# PG04__BALANCER.net
KiCad netlist of a schematic drawn in Altium Designer
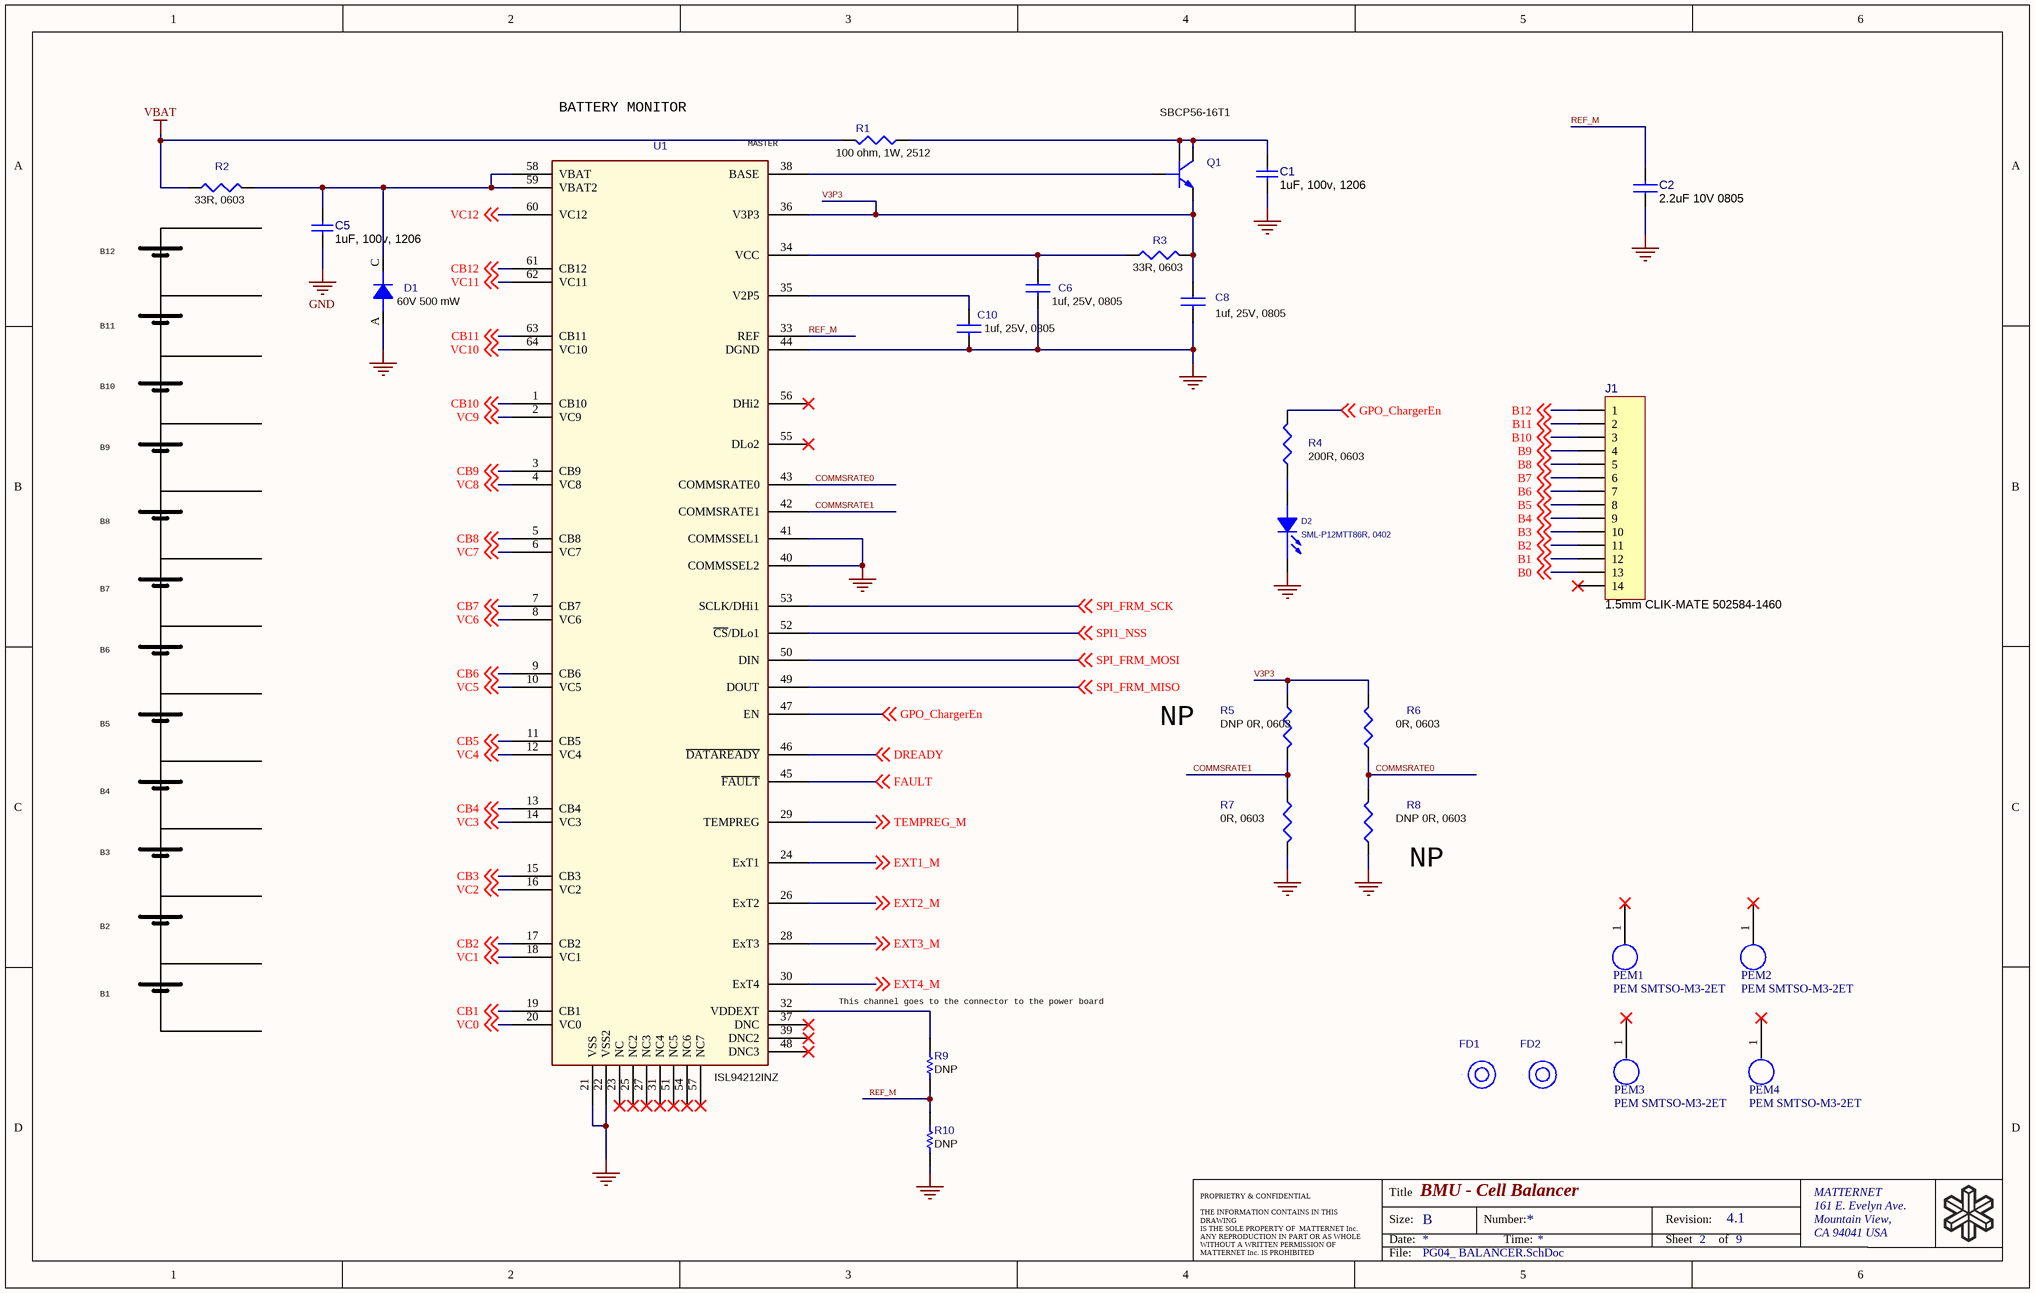
[diagram p0: PG04_ BALANCER.SchDoc]

(export (version "E")
  (design (tool "Eeschema 10.0.6"))
  (components
    (comp (ref "C1")
      (value "1uF, 100v, 1206")
      (footprint "C1206")
      (description "CAP CER 1UF 100V X7R 1210 AUTO F")
      (fields
        (field (name "MANUFACTURER") "KEMET")
        (field (name "MANUFACTURER PART NUMBER") "C1210X105K1RACAUTO")
      )
      (libsource (lib "Miscellaneous Devices") (part "Cap"))
    )
    (comp (ref "C2")
      (value "2.2uF 10V 0805")
      (footprint "C0805")
      (description "CAP CER 2.2UF 10V 10% X7R 0805")
      (fields
        (field (name "MANUFACTURER") "KEMET")
        (field (name "MANUFACTURER PART NUMBER") "C0805X225K8RACAUTO")
      )
      (libsource (lib "*") (part "CAP-Generic-0805"))
    )
    (comp (ref "C5")
      (value "1uF, 100v, 1206")
      (footprint "C1206")
      (description "CAP CER 1UF 100V X7R 1210 AUTO F")
      (fields
        (field (name "MANUFACTURER") "KEMET")
        (field (name "MANUFACTURER PART NUMBER") "C1210X105K1RACAUTO")
      )
      (libsource (lib "Miscellaneous Devices") (part "Cap"))
    )
    (comp (ref "C6")
      (value "1uf, 25V, 0805")
      (footprint "C0805")
      (description "CAP CER 1UF 25V X7R 0805")
      (fields
        (field (name "MANUFACTURER") "Murata")
        (field (name "MANUFACTURER PART NUMBER") "GCJ21BR71E105KA12L")
      )
      (libsource (lib "*") (part "CAP-Generic-0402"))
    )
    (comp (ref "C8")
      (value "1uf, 25V, 0805")
      (footprint "C0805")
      (description "CAP CER 1UF 25V X7R 0805")
      (fields
        (field (name "MANUFACTURER") "Murata")
        (field (name "MANUFACTURER PART NUMBER") "GCJ21BR71E105KA12L")
      )
      (libsource (lib "*") (part "CAP-Generic-0402"))
    )
    (comp (ref "C10")
      (value "1uf, 25V, 0805")
      (footprint "C0805")
      (description "CAP CER 1UF 25V X7R 0805")
      (fields
        (field (name "MANUFACTURER") "Murata")
        (field (name "MANUFACTURER PART NUMBER") "GCJ21BR71E105KA12L")
      )
      (libsource (lib "*") (part "CAP-Generic-0402"))
    )
    (comp (ref "D1")
      (value "60V 500 mW")
      (footprint "SOD-123")
      (description "DIODE ZENER 60V 500MW SOD123")
      (fields
        (field (name "MANUFACTURER") "ON Semiconductor")
        (field (name "MANUFACTURER PART NUMBER") "MMSZ5264BT1G")
      )
      (libsource (lib "*") (part "DIO-GENERIC"))
    )
    (comp (ref "D2")
      (value "SML-P12MTT86R, 0402")
      (footprint "D0402")
      (libsource (lib "M2_V8_BMU_V1.0") (part "LED-GENERIC"))
    )
    (comp (ref "FD1")
      (value "FIDUCIAL_REF")
      (footprint "FIDUCIAL_REFDES")
      (libsource (lib "*") (part "FIDUCIAL_REF"))
    )
    (comp (ref "FD2")
      (value "FIDUCIAL_REF")
      (footprint "FIDUCIAL_REFDES")
      (libsource (lib "*") (part "FIDUCIAL_REF"))
    )
    (comp (ref "J1")
      (value "1.5mm CLIK-MATE 502584-1460")
      (footprint "CONN14_1p5mm_SM")
      (description "CONN RCPT 14POS 0.059 TIN SMD")
      (fields (field (name "MANUFACTURER") "Molex") (field (name "MANUFACTURER PART NUMBER") "502584-1460"))
      (libsource (lib "Miscellaneous Connectors") (part "Header 14"))
    )
    (comp (ref "PEM1")
      (value "PEM SMTSO-M3-2ET")
      (footprint "SMTSO-M3-2ET")
      (description "PEM Nut, M3 thread")
      (libsource (lib "RonsLib1") (part "PEM SMTSO-M3-2ET"))
    )
    (comp (ref "PEM2")
      (value "PEM SMTSO-M3-2ET")
      (footprint "SMTSO-M3-2ET")
      (description "PEM Nut, M3 thread")
      (libsource (lib "RonsLib1") (part "PEM SMTSO-M3-2ET"))
    )
    (comp (ref "PEM3")
      (value "PEM SMTSO-M3-2ET")
      (footprint "SMTSO-M3-2ET")
      (description "PEM Nut, M3 thread")
      (libsource (lib "RonsLib1") (part "PEM SMTSO-M3-2ET"))
    )
    (comp (ref "PEM4")
      (value "PEM SMTSO-M3-2ET")
      (footprint "SMTSO-M3-2ET")
      (description "PEM Nut, M3 thread")
      (libsource (lib "RonsLib1") (part "PEM SMTSO-M3-2ET"))
    )
    (comp (ref "Q1")
      (value "SBCP56-16T1")
      (footprint "SOT-223")
      (description "TRANS NPN 80V 1.0A SOT-223")
      (fields
        (field (name "MANUFACTURER") "ON Semiconductor")
        (field (name "MANUFACTURER PART NUMBER") "SBCP56-16T1G")
      )
      (libsource (lib "*") (part "Trans-Generic_2"))
    )
    (comp (ref "R1")
      (value "100 ohm, 1W, 2512")
      (footprint "2512")
      (description "RES SMD 100 OHM 5% 1W 2512")
      (fields
        (field (name "MANUFACTURER") "Panasonic")
        (field (name "MANUFACTURER PART NUMBER") "ERJ-1TYJ101U")
      )
      (libsource (lib "*") (part "R-Generic"))
    )
    (comp (ref "R2")
      (value "33R, 0603")
      (footprint "R0603")
      (description "RES SMD 33 OHM 1% 1/10W 0603")
      (fields
        (field (name "MANUFACTURER") "Yageo")
        (field (name "MANUFACTURER PART NUMBER") "AC0603FR-0733RL")
      )
      (libsource (lib "*") (part "R-Generic-0603"))
    )
    (comp (ref "R3")
      (value "33R, 0603")
      (footprint "R0603")
      (description "RES SMD 33 OHM 1% 1/10W 0603")
      (fields
        (field (name "MANUFACTURER") "Yageo")
        (field (name "MANUFACTURER PART NUMBER") "AC0603FR-0733RL")
      )
      (libsource (lib "*") (part "R-Generic-0603"))
    )
    (comp (ref "R4")
      (value "200R, 0603")
      (footprint "R0603")
      (description "RES SMD 200 OHM 1% 1/10W 0603")
      (fields
        (field (name "MANUFACTURER") "Yageo")
        (field (name "MANUFACTURER PART NUMBER") "AC0603FR-07200RL")
      )
      (libsource (lib "*") (part "R-Generic-0603"))
    )
    (comp (ref "R5")
      (value "DNP 0R, 0603")
      (footprint "R0603")
      (description "DNP")
      (libsource (lib "*") (part "R-Generic-0402"))
    )
    (comp (ref "R6")
      (value "0R, 0603")
      (footprint "R0603")
      (description "RES SMD 0 OHM JUMPER 1/10W 0603")
      (fields
        (field (name "MANUFACTURER") "Yageo")
        (field (name "MANUFACTURER PART NUMBER") "RC0603FR-070RL")
      )
      (libsource (lib "*") (part "R-Generic-0402"))
    )
    (comp (ref "R7")
      (value "0R, 0603")
      (footprint "R0603")
      (description "RES SMD 0 OHM JUMPER 1/10W 0603")
      (fields
        (field (name "MANUFACTURER") "Yageo")
        (field (name "MANUFACTURER PART NUMBER") "RC0603FR-070RL")
      )
      (libsource (lib "*") (part "R-Generic-0402"))
    )
    (comp (ref "R8")
      (value "DNP 0R, 0603")
      (footprint "R0603")
      (description "DNP")
      (libsource (lib "*") (part "R-Generic-0402"))
    )
    (comp (ref "R9")
      (value "DNP")
      (footprint "R0402")
      (description "Resistor")
      (fields (field (name "PUBLISHER") "Altium Limited"))
      (libsource (lib "Miscellaneous Devices") (part "Res1"))
    )
    (comp (ref "R10")
      (value "DNP")
      (footprint "R0402")
      (description "Resistor")
      (fields (field (name "PUBLISHER") "Altium Limited"))
      (libsource (lib "Miscellaneous Devices") (part "Res1"))
    )
    (comp (ref "U1")
      (value "ISL94212INZ")
      (footprint "TQFP-64")
      (description "Battery Management Multi-Cell Li-Ion Battery Manager")
      (fields (field (name "MANUFACTURER") "Renesas"))
      (libsource (lib "M2_V8_BMU_V1.0") (part "BATTMAN-ISL94212INZ-700-498"))
    )
  )
  (nets
    (net (code "1") (name "/COMMSRATE0") (class "Default")
      (node (ref "R6") (pin "2") (pinfunction "2_2") (pintype "passive"))
      (node (ref "R8") (pin "1") (pinfunction "1_1") (pintype "passive"))
      (node (ref "U1") (pin "43") (pinfunction "COMMSRATE0_43") (pintype "passive"))
    )
    (net (code "2") (name "/COMMSRATE1") (class "Default")
      (node (ref "R5") (pin "2") (pinfunction "2_2") (pintype "passive"))
      (node (ref "R7") (pin "1") (pinfunction "1_1") (pintype "passive"))
      (node (ref "U1") (pin "42") (pinfunction "COMMSRATE1_42") (pintype "passive"))
    )
    (net (code "3") (name "/REF_M") (class "Default")
      (node (ref "C2") (pin "2") (pinfunction "2_2") (pintype "passive"))
      (node (ref "R10") (pin "2") (pinfunction "2_2") (pintype "passive"))
      (node (ref "R9") (pin "1") (pinfunction "1_1") (pintype "passive"))
      (node (ref "U1") (pin "33") (pinfunction "REF_33") (pintype "passive"))
    )
    (net (code "4") (name "/V3P3") (class "Default")
      (node (ref "C8") (pin "1") (pinfunction "1_1") (pintype "passive"))
      (node (ref "Q1") (pin "3") (pinfunction "E_3") (pintype "passive"))
      (node (ref "R3") (pin "2") (pinfunction "2_2") (pintype "passive"))
      (node (ref "R5") (pin "1") (pinfunction "1_1") (pintype "passive"))
      (node (ref "R6") (pin "1") (pinfunction "1_1") (pintype "passive"))
      (node (ref "U1") (pin "36") (pinfunction "V3P3_36") (pintype "passive"))
    )
    (net (code "5") (name "B0") (class "Default")
      (node (ref "J1") (pin "13") (pinfunction "13_13") (pintype "passive"))
    )
    (net (code "6") (name "B1") (class "Default")
      (node (ref "J1") (pin "12") (pinfunction "12_12") (pintype "passive"))
    )
    (net (code "7") (name "B2") (class "Default")
      (node (ref "J1") (pin "11") (pinfunction "11_11") (pintype "passive"))
    )
    (net (code "8") (name "B3") (class "Default")
      (node (ref "J1") (pin "10") (pinfunction "10_10") (pintype "passive"))
    )
    (net (code "9") (name "B4") (class "Default")
      (node (ref "J1") (pin "9") (pinfunction "9_9") (pintype "passive"))
    )
    (net (code "10") (name "B5") (class "Default")
      (node (ref "J1") (pin "8") (pinfunction "8_8") (pintype "passive"))
    )
    (net (code "11") (name "B6") (class "Default")
      (node (ref "J1") (pin "7") (pinfunction "7_7") (pintype "passive"))
    )
    (net (code "12") (name "B7") (class "Default")
      (node (ref "J1") (pin "6") (pinfunction "6_6") (pintype "passive"))
    )
    (net (code "13") (name "B8") (class "Default")
      (node (ref "J1") (pin "5") (pinfunction "5_5") (pintype "passive"))
    )
    (net (code "14") (name "B9") (class "Default")
      (node (ref "J1") (pin "4") (pinfunction "4_4") (pintype "passive"))
    )
    (net (code "15") (name "B10") (class "Default")
      (node (ref "J1") (pin "3") (pinfunction "3_3") (pintype "passive"))
    )
    (net (code "16") (name "B11") (class "Default")
      (node (ref "J1") (pin "2") (pinfunction "2_2") (pintype "passive"))
    )
    (net (code "17") (name "B12") (class "Default")
      (node (ref "J1") (pin "1") (pinfunction "1_1") (pintype "passive"))
    )
    (net (code "18") (name "CB1") (class "Default")
      (node (ref "U1") (pin "19") (pinfunction "CB1_19") (pintype "passive"))
    )
    (net (code "19") (name "CB2") (class "Default")
      (node (ref "U1") (pin "17") (pinfunction "CB2_17") (pintype "passive"))
    )
    (net (code "20") (name "CB3") (class "Default")
      (node (ref "U1") (pin "15") (pinfunction "CB3_15") (pintype "passive"))
    )
    (net (code "21") (name "CB4") (class "Default")
      (node (ref "U1") (pin "13") (pinfunction "CB4_13") (pintype "passive"))
    )
    (net (code "22") (name "CB5") (class "Default")
      (node (ref "U1") (pin "11") (pinfunction "CB5_11") (pintype "passive"))
    )
    (net (code "23") (name "CB6") (class "Default")
      (node (ref "U1") (pin "9") (pinfunction "CB6_9") (pintype "passive"))
    )
    (net (code "24") (name "CB7") (class "Default")
      (node (ref "U1") (pin "7") (pinfunction "CB7_7") (pintype "passive"))
    )
    (net (code "25") (name "CB8") (class "Default")
      (node (ref "U1") (pin "5") (pinfunction "CB8_5") (pintype "passive"))
    )
    (net (code "26") (name "CB9") (class "Default")
      (node (ref "U1") (pin "3") (pinfunction "CB9_3") (pintype "passive"))
    )
    (net (code "27") (name "CB10") (class "Default")
      (node (ref "U1") (pin "1") (pinfunction "CB10_1") (pintype "passive"))
    )
    (net (code "28") (name "CB11") (class "Default")
      (node (ref "U1") (pin "63") (pinfunction "CB11_63") (pintype "passive"))
    )
    (net (code "29") (name "CB12") (class "Default")
      (node (ref "U1") (pin "61") (pinfunction "CB12_61") (pintype "passive"))
    )
    (net (code "30") (name "DREADY") (class "Default")
      (node (ref "U1") (pin "46") (pinfunction "~{DATAREADY}_46") (pintype "passive"))
    )
    (net (code "31") (name "EXT1_M") (class "Default")
      (node (ref "U1") (pin "24") (pinfunction "ExT1_24") (pintype "passive"))
    )
    (net (code "32") (name "EXT2_M") (class "Default")
      (node (ref "U1") (pin "26") (pinfunction "ExT2_26") (pintype "passive"))
    )
    (net (code "33") (name "EXT3_M") (class "Default")
      (node (ref "U1") (pin "28") (pinfunction "ExT3_28") (pintype "passive"))
    )
    (net (code "34") (name "EXT4_M") (class "Default")
      (node (ref "U1") (pin "30") (pinfunction "ExT4_30") (pintype "passive"))
    )
    (net (code "35") (name "FAULT") (class "Default")
      (node (ref "U1") (pin "45") (pinfunction "~{FAULT}_45") (pintype "passive"))
    )
    (net (code "36") (name "GND") (class "Default")
      (node (ref "C1") (pin "2") (pinfunction "2_2") (pintype "passive"))
      (node (ref "C10") (pin "2") (pinfunction "2_2") (pintype "passive"))
      (node (ref "C2") (pin "1") (pinfunction "1_1") (pintype "passive"))
      (node (ref "C5") (pin "1") (pinfunction "1_1") (pintype "passive"))
      (node (ref "C6") (pin "2") (pinfunction "2_2") (pintype "passive"))
      (node (ref "C8") (pin "2") (pinfunction "2_2") (pintype "passive"))
      (node (ref "D1") (pin "A") (pinfunction "ANODE_A") (pintype "passive"))
      (node (ref "D2") (pin "C") (pinfunction "CATHODE_C") (pintype "passive"))
      (node (ref "R10") (pin "1") (pinfunction "1_1") (pintype "passive"))
      (node (ref "R7") (pin "2") (pinfunction "2_2") (pintype "passive"))
      (node (ref "R8") (pin "2") (pinfunction "2_2") (pintype "passive"))
      (node (ref "U1") (pin "21") (pinfunction "VSS_21") (pintype "passive"))
      (node (ref "U1") (pin "22") (pinfunction "VSS2_22") (pintype "passive"))
      (node (ref "U1") (pin "40") (pinfunction "COMMSSEL2_40") (pintype "passive"))
      (node (ref "U1") (pin "41") (pinfunction "COMMSSEL1_41") (pintype "passive"))
      (node (ref "U1") (pin "44") (pinfunction "DGND_44") (pintype "passive"))
    )
    (net (code "37") (name "GPO_ChargerEn") (class "Default")
      (node (ref "R4") (pin "2") (pinfunction "2_2") (pintype "passive"))
      (node (ref "U1") (pin "47") (pinfunction "EN_47") (pintype "passive"))
    )
    (net (code "38") (name "Net-(C1-Pad1)") (class "Default")
      (node (ref "C1") (pin "1") (pinfunction "1_1") (pintype "passive"))
      (node (ref "Q1") (pin "2") (pinfunction "C_2") (pintype "power_in"))
      (node (ref "Q1") (pin "4") (pinfunction "C_4") (pintype "power_in"))
      (node (ref "R1") (pin "1") (pinfunction "1_1") (pintype "passive"))
    )
    (net (code "39") (name "Net-(D1-CATHODE)") (class "Default")
      (node (ref "C5") (pin "2") (pinfunction "2_2") (pintype "passive"))
      (node (ref "D1") (pin "C") (pinfunction "CATHODE_C") (pintype "passive"))
      (node (ref "R2") (pin "2") (pinfunction "2_2") (pintype "passive"))
      (node (ref "U1") (pin "58") (pinfunction "VBAT_58") (pintype "passive"))
      (node (ref "U1") (pin "59") (pinfunction "VBAT2_59") (pintype "passive"))
    )
    (net (code "40") (name "Net-(D2-ANODE)") (class "Default")
      (node (ref "D2") (pin "A") (pinfunction "ANODE_A") (pintype "passive"))
      (node (ref "R4") (pin "1") (pinfunction "1_1") (pintype "passive"))
    )
    (net (code "41") (name "Net-(Q1-B)") (class "Default")
      (node (ref "Q1") (pin "1") (pinfunction "B_1") (pintype "passive"))
      (node (ref "U1") (pin "38") (pinfunction "BASE_38") (pintype "passive"))
    )
    (net (code "42") (name "Net-(U1-V2P5)") (class "Default")
      (node (ref "C10") (pin "1") (pinfunction "1_1") (pintype "passive"))
      (node (ref "U1") (pin "35") (pinfunction "V2P5_35") (pintype "passive"))
    )
    (net (code "43") (name "Net-(U1-VCC)") (class "Default")
      (node (ref "C6") (pin "1") (pinfunction "1_1") (pintype "passive"))
      (node (ref "R3") (pin "1") (pinfunction "1_1") (pintype "passive"))
      (node (ref "U1") (pin "34") (pinfunction "VCC_34") (pintype "passive"))
    )
    (net (code "44") (name "Net-(U1-VDDEXT)") (class "Default")
      (node (ref "R9") (pin "2") (pinfunction "2_2") (pintype "passive"))
      (node (ref "U1") (pin "32") (pinfunction "VDDEXT_32") (pintype "passive"))
    )
    (net (code "45") (name "SPI1_NSS") (class "Default")
      (node (ref "U1") (pin "52") (pinfunction "~{CS}/DLo1_52") (pintype "passive"))
    )
    (net (code "46") (name "SPI_FRM_MISO") (class "Default")
      (node (ref "U1") (pin "49") (pinfunction "DOUT_49") (pintype "passive"))
    )
    (net (code "47") (name "SPI_FRM_MOSI") (class "Default")
      (node (ref "U1") (pin "50") (pinfunction "DIN_50") (pintype "passive"))
    )
    (net (code "48") (name "SPI_FRM_SCK") (class "Default")
      (node (ref "U1") (pin "53") (pinfunction "SCLK/DHi1_53") (pintype "passive"))
    )
    (net (code "49") (name "TEMPREG_M") (class "Default")
      (node (ref "U1") (pin "29") (pinfunction "TEMPREG_29") (pintype "passive"))
    )
    (net (code "50") (name "VBAT") (class "Default")
      (node (ref "R1") (pin "2") (pinfunction "2_2") (pintype "passive"))
      (node (ref "R2") (pin "1") (pinfunction "1_1") (pintype "passive"))
    )
    (net (code "51") (name "VC0") (class "Default")
      (node (ref "U1") (pin "20") (pinfunction "VC0_20") (pintype "passive"))
    )
    (net (code "52") (name "VC1") (class "Default")
      (node (ref "U1") (pin "18") (pinfunction "VC1_18") (pintype "passive"))
    )
    (net (code "53") (name "VC2") (class "Default")
      (node (ref "U1") (pin "16") (pinfunction "VC2_16") (pintype "passive"))
    )
    (net (code "54") (name "VC3") (class "Default")
      (node (ref "U1") (pin "14") (pinfunction "VC3_14") (pintype "passive"))
    )
    (net (code "55") (name "VC4") (class "Default")
      (node (ref "U1") (pin "12") (pinfunction "VC4_12") (pintype "passive"))
    )
    (net (code "56") (name "VC5") (class "Default")
      (node (ref "U1") (pin "10") (pinfunction "VC5_10") (pintype "passive"))
    )
    (net (code "57") (name "VC6") (class "Default")
      (node (ref "U1") (pin "8") (pinfunction "VC6_8") (pintype "passive"))
    )
    (net (code "58") (name "VC7") (class "Default")
      (node (ref "U1") (pin "6") (pinfunction "VC7_6") (pintype "passive"))
    )
    (net (code "59") (name "VC8") (class "Default")
      (node (ref "U1") (pin "4") (pinfunction "VC8_4") (pintype "passive"))
    )
    (net (code "60") (name "VC9") (class "Default")
      (node (ref "U1") (pin "2") (pinfunction "VC9_2") (pintype "passive"))
    )
    (net (code "61") (name "VC10") (class "Default")
      (node (ref "U1") (pin "64") (pinfunction "VC10_64") (pintype "passive"))
    )
    (net (code "62") (name "VC11") (class "Default")
      (node (ref "U1") (pin "62") (pinfunction "VC11_62") (pintype "passive"))
    )
    (net (code "63") (name "VC12") (class "Default")
      (node (ref "U1") (pin "60") (pinfunction "VC12_60") (pintype "passive"))
    )
    (net (code "64") (name "unconnected-(FD1-Pad1)") (class "Default")
      (node (ref "FD1") (pin "1") (pinfunction "1_1") (pintype "passive"))
    )
    (net (code "65") (name "unconnected-(FD2-Pad1)") (class "Default")
      (node (ref "FD2") (pin "1") (pinfunction "1_1") (pintype "passive"))
    )
    (net (code "66") (name "unconnected-(J1-Pad14)") (class "Default")
      (node (ref "J1") (pin "14") (pinfunction "14_14") (pintype "passive+no_connect"))
    )
    (net (code "67") (name "unconnected-(PEM1-Pad1)") (class "Default")
      (node (ref "PEM1") (pin "1") (pintype "passive+no_connect"))
    )
    (net (code "68") (name "unconnected-(PEM2-Pad1)") (class "Default")
      (node (ref "PEM2") (pin "1") (pintype "passive+no_connect"))
    )
    (net (code "69") (name "unconnected-(PEM3-Pad1)") (class "Default")
      (node (ref "PEM3") (pin "1") (pintype "passive+no_connect"))
    )
    (net (code "70") (name "unconnected-(PEM4-Pad1)") (class "Default")
      (node (ref "PEM4") (pin "1") (pintype "passive+no_connect"))
    )
    (net (code "71") (name "unconnected-(U1-DHi2-Pad56)") (class "Default")
      (node (ref "U1") (pin "56") (pinfunction "DHi2_56") (pintype "passive+no_connect"))
    )
    (net (code "72") (name "unconnected-(U1-DLo2-Pad55)") (class "Default")
      (node (ref "U1") (pin "55") (pinfunction "DLo2_55") (pintype "passive+no_connect"))
    )
    (net (code "73") (name "unconnected-(U1-DNC-Pad37)") (class "Default")
      (node (ref "U1") (pin "37") (pinfunction "DNC_37") (pintype "passive+no_connect"))
    )
    (net (code "74") (name "unconnected-(U1-DNC2-Pad39)") (class "Default")
      (node (ref "U1") (pin "39") (pinfunction "DNC2_39") (pintype "passive+no_connect"))
    )
    (net (code "75") (name "unconnected-(U1-DNC3-Pad48)") (class "Default")
      (node (ref "U1") (pin "48") (pinfunction "DNC3_48") (pintype "passive+no_connect"))
    )
    (net (code "76") (name "unconnected-(U1-NC-Pad23)") (class "Default")
      (node (ref "U1") (pin "23") (pinfunction "NC_23") (pintype "passive+no_connect"))
    )
    (net (code "77") (name "unconnected-(U1-NC2-Pad25)") (class "Default")
      (node (ref "U1") (pin "25") (pinfunction "NC2_25") (pintype "passive+no_connect"))
    )
    (net (code "78") (name "unconnected-(U1-NC3-Pad27)") (class "Default")
      (node (ref "U1") (pin "27") (pinfunction "NC3_27") (pintype "passive+no_connect"))
    )
    (net (code "79") (name "unconnected-(U1-NC4-Pad31)") (class "Default")
      (node (ref "U1") (pin "31") (pinfunction "NC4_31") (pintype "passive+no_connect"))
    )
    (net (code "80") (name "unconnected-(U1-NC5-Pad51)") (class "Default")
      (node (ref "U1") (pin "51") (pinfunction "NC5_51") (pintype "passive+no_connect"))
    )
    (net (code "81") (name "unconnected-(U1-NC6-Pad54)") (class "Default")
      (node (ref "U1") (pin "54") (pinfunction "NC6_54") (pintype "passive+no_connect"))
    )
    (net (code "82") (name "unconnected-(U1-NC7-Pad57)") (class "Default")
      (node (ref "U1") (pin "57") (pinfunction "NC7_57") (pintype "passive+no_connect"))
    )
  )
)
